# USB_Downstream_Type_C_Port_4.net
KiCad netlist of a schematic drawn in Altium Designer
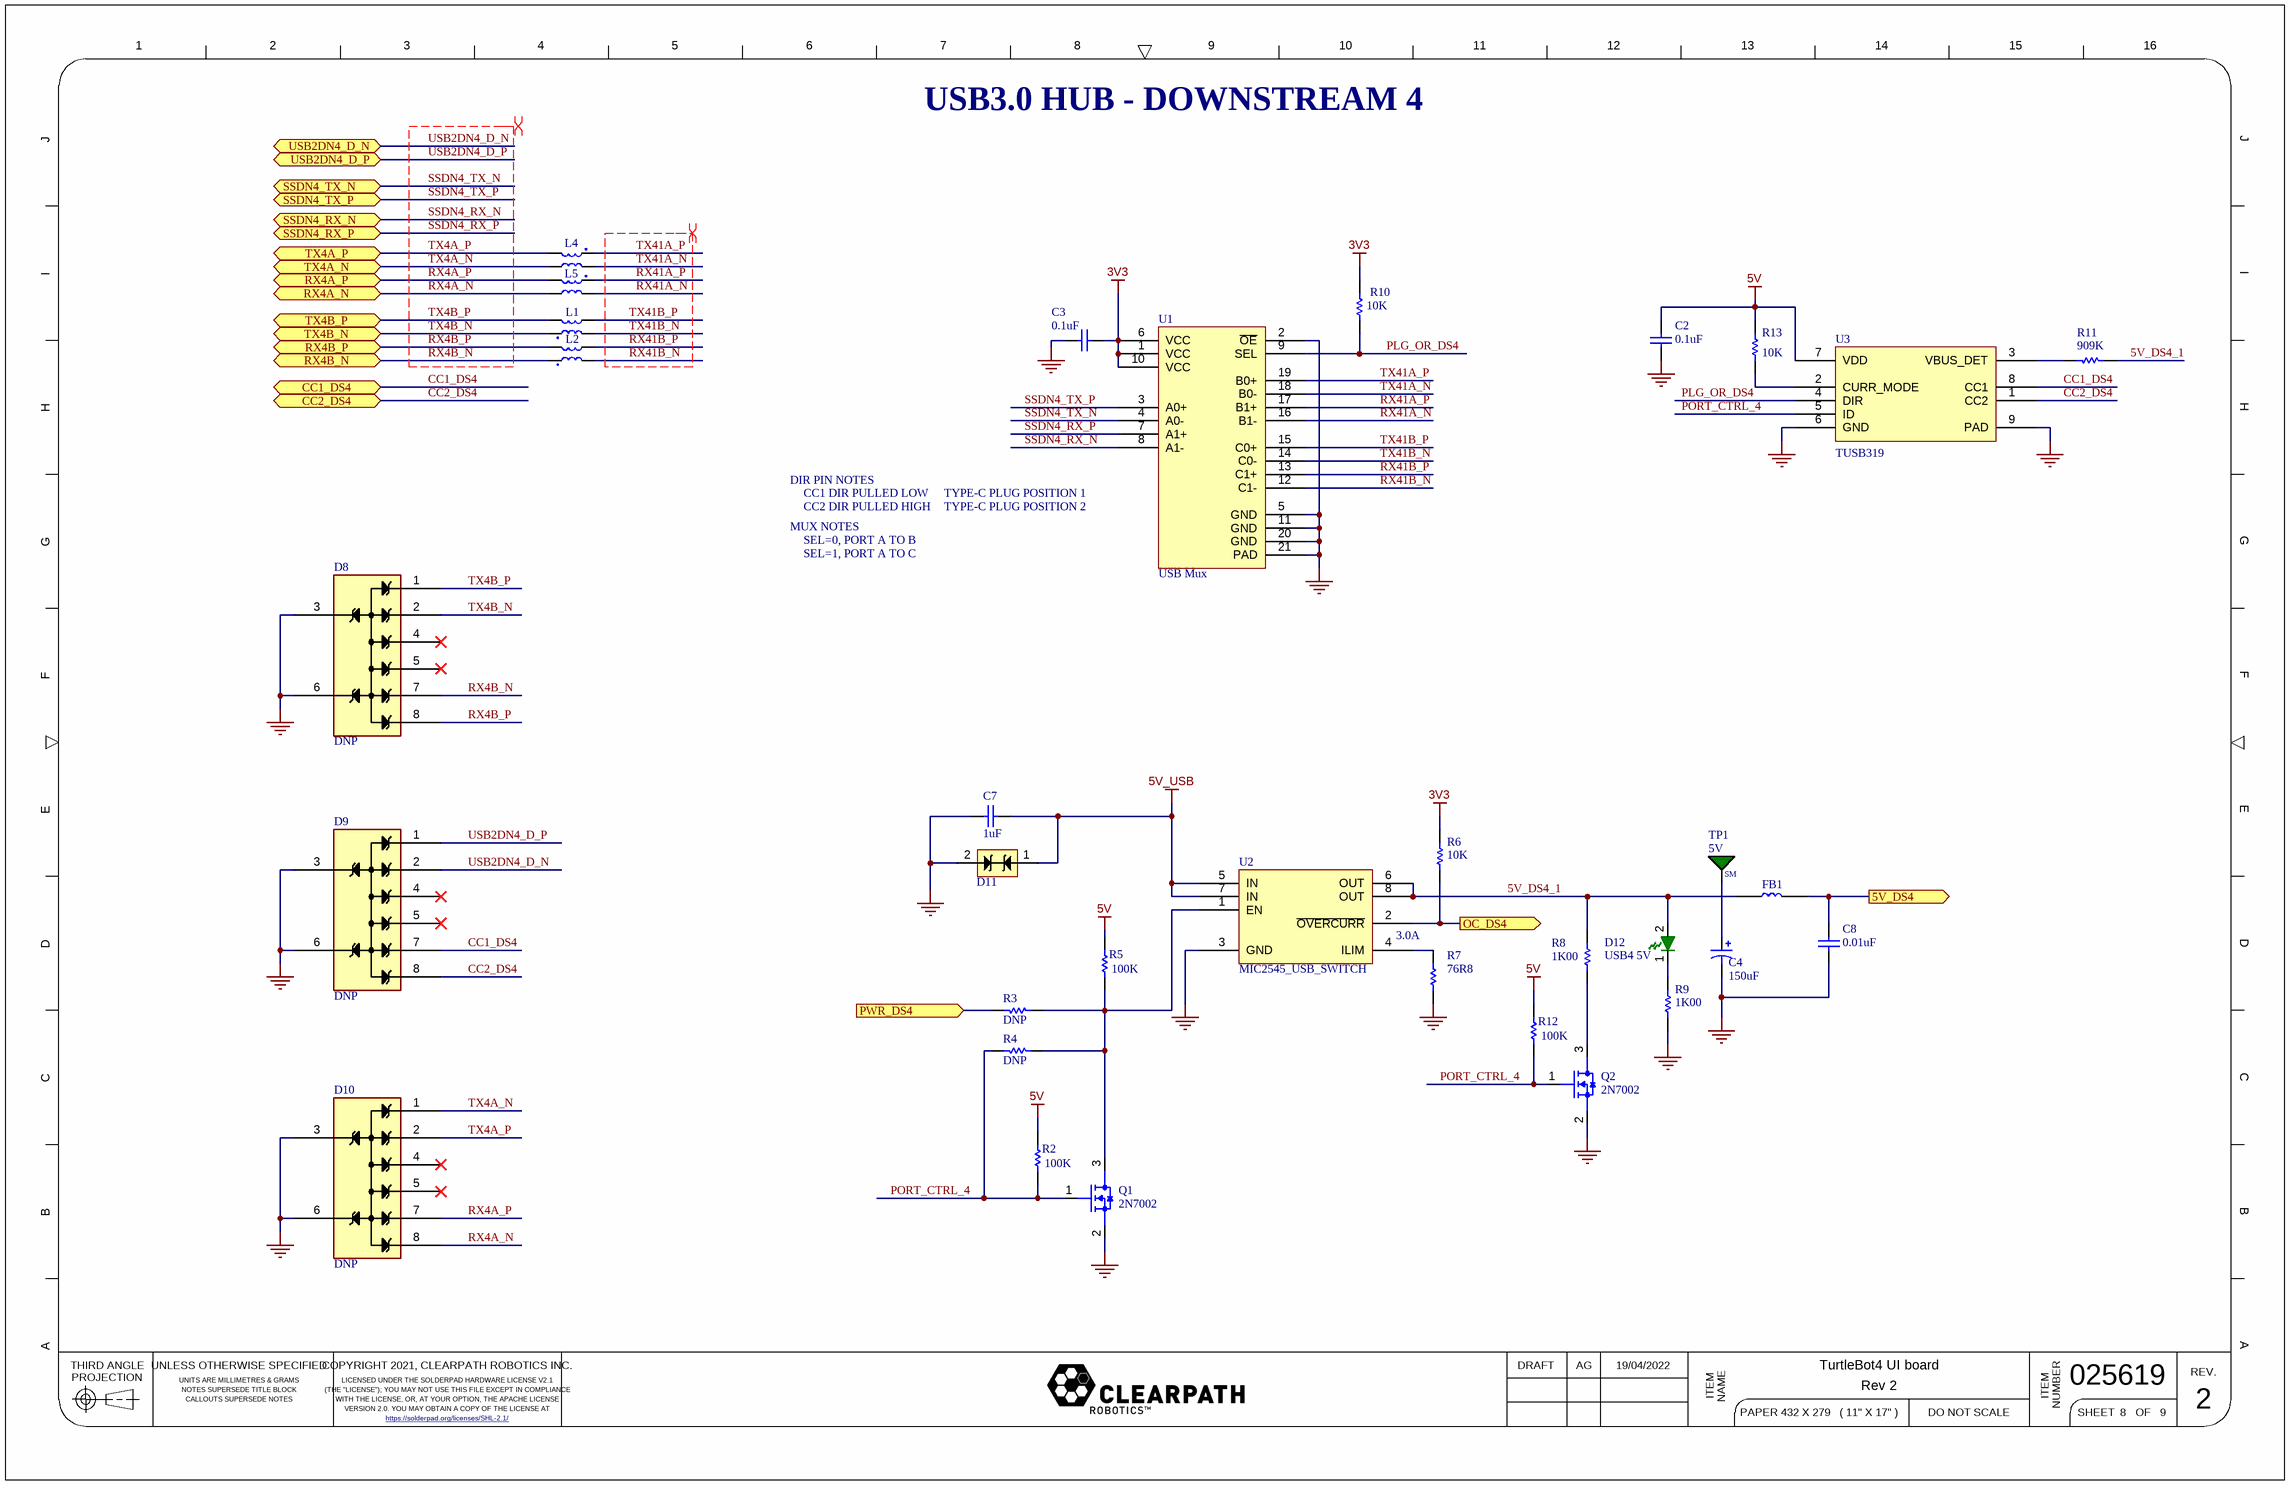
[diagram p0: USB Downstream Type C Port 4.SchDoc]

(export (version "E")
  (design (tool "Eeschema 10.0.6"))
  (components
    (comp (ref "C2")
      (value "0.1uF")
      (footprint "C0805")
      (description "Capacitor")
      (fields (field (name "TOLERANCE") "10%") (field (name "VOLTAGE") "50V"))
      (libsource (lib "CPR_CommonDevices") (part "Capacitor _SMT"))
    )
    (comp (ref "C3")
      (value "0.1uF")
      (footprint "C0805")
      (description "Capacitor")
      (fields (field (name "TOLERANCE") "10%") (field (name "VOLTAGE") "50V"))
      (libsource (lib "CPR_CommonDevices") (part "Capacitor _SMT"))
    )
    (comp (ref "C4")
      (value "150uF")
      (footprint "T494D157K016AT:CAPMP7.6X4.3_3.1N_KEM-M")
      (description "CAP TANT 150UF 10% 16V 2917")
      (fields (field (name "VOLTAGE") "16V") (field (name "TOLERANCE") "10%"))
      (libsource (lib "Miscellaneous Devices") (part "Cap Pol1"))
    )
    (comp (ref "C7")
      (value "1uF")
      (footprint "C0805")
      (description "Capacitor")
      (fields (field (name "TOLERANCE") "-20 +80") (field (name "VOLTAGE") "50V"))
      (libsource (lib "CPR_CommonDevices") (part "Capacitor _SMT"))
    )
    (comp (ref "C8")
      (value "0.01uF")
      (footprint "C0805")
      (description "Capacitor")
      (fields (field (name "TOLERANCE") "10%") (field (name "VOLTAGE") "50V"))
      (libsource (lib "CPR_CommonDevices") (part "Capacitor _SMT"))
    )
    (comp (ref "D8")
      (value "DNP")
      (footprint "ESD7016")
      (description "USB3 TVS diode assy")
      (fields (field (name "MFG") "ON Semi"))
      (libsource (lib "ONSemi_ESD7016") (part "ESD7016"))
    )
    (comp (ref "D9")
      (value "DNP")
      (footprint "ESD7016")
      (description "USB3 TVS diode assy")
      (fields (field (name "MFG") "ON Semi"))
      (libsource (lib "ONSemi_ESD7016") (part "ESD7016"))
    )
    (comp (ref "D10")
      (value "DNP")
      (footprint "ESD7016")
      (description "USB3 TVS diode assy")
      (fields (field (name "MFG") "ON Semi"))
      (libsource (lib "ONSemi_ESD7016") (part "ESD7016"))
    )
    (comp (ref "D11")
      (value "TVS DIODE BIDIR 15V SMC")
      (footprint "General PCB Library:DO-214AA")
      (description "TVS 600W 15V BI-DIR DO-214AA")
      (fields (field (name "MFG") "Littelfuse Inc."))
      (libsource (lib "SMBJ15CA") (part "TVS DIODE BIDIR 15V SMC"))
    )
    (comp (ref "D12")
      (value "USB4 5V")
      (footprint "LED_0805_GRN")
      (description "Green LED")
      (fields (field (name "MFG") "LiteOn"))
      (libsource (lib "Green LED") (part "GREEN_LED"))
    )
    (comp (ref "FB1")
      (value "742792602")
      (footprint "General PCB Library:R0603")
      (description "60 Ohms 1 Signal Line Ferrite Bead 0603 (1608 Metric) 3A 40mOhm")
      (libsource (lib "742792602") (part "742792602"))
    )
    (comp (ref "L1")
      (value "CMC 100MA 2LN 90 OHM SMD2")
      (footprint "cmc_90_ohms:cmc_90_ohms")
      (description "Line Common Mode Choke Surface Mount 90 Ohms 100mA DCR 5Ohm")
      (libsource (lib "cmc_90_ohms") (part "CMC 90_Ohms"))
    )
    (comp (ref "L2")
      (value "CMC 100MA 2LN 90 OHM SMD2")
      (footprint "cmc_90_ohms:cmc_90_ohms")
      (description "Line Common Mode Choke Surface Mount 90 Ohms 100mA DCR 5Ohm")
      (libsource (lib "cmc_90_ohms") (part "CMC 90_Ohms"))
    )
    (comp (ref "L4")
      (value "CMC 100MA 2LN 90 OHM SMD2")
      (footprint "cmc_90_ohms:cmc_90_ohms")
      (description "Line Common Mode Choke Surface Mount 90 Ohms 100mA DCR 5Ohm")
      (libsource (lib "cmc_90_ohms") (part "CMC 90_Ohms"))
    )
    (comp (ref "L5")
      (value "CMC 100MA 2LN 90 OHM SMD2")
      (footprint "cmc_90_ohms:cmc_90_ohms")
      (description "Line Common Mode Choke Surface Mount 90 Ohms 100mA DCR 5Ohm")
      (libsource (lib "cmc_90_ohms") (part "CMC 90_Ohms"))
    )
    (comp (ref "Q1")
      (value "NFET")
      (footprint "SOT-23-3")
      (fields (field (name "MFG PN") "2N7002") (field (name "MFG") "ON Semi"))
      (libsource (lib "NFET_SINGLE") (part "NFET_SNGL"))
    )
    (comp (ref "Q2")
      (value "NFET")
      (footprint "SOT-23-3")
      (fields (field (name "MFG PN") "2N7002") (field (name "MFG") "ON Semi"))
      (libsource (lib "NFET_SINGLE") (part "NFET_SNGL"))
    )
    (comp (ref "R2")
      (value "100K")
      (footprint "R0805")
      (description "Resistor")
      (fields (field (name "TOLERANCE") "1%") (field (name "MFG") "Yageo"))
      (libsource (lib "") (part "Resistor_SMT_1"))
    )
    (comp (ref "R3")
      (value "DNP")
      (footprint "R0805")
      (description "Resistor")
      (fields (field (name "MFG") "Yageo") (field (name "Comment") "Resistor_SMT"))
      (libsource (lib "CPR_CommonDevices") (part "Resistor_SMT"))
    )
    (comp (ref "R4")
      (value "DNP")
      (footprint "R0805")
      (description "Resistor")
      (fields (field (name "MFG") "Yageo") (field (name "Comment") "Resistor_SMT"))
      (libsource (lib "CPR_CommonDevices") (part "Resistor_SMT"))
    )
    (comp (ref "R5")
      (value "100K")
      (footprint "R0805")
      (description "Resistor")
      (fields (field (name "TOLERANCE") "1%") (field (name "MFG") "Yageo"))
      (libsource (lib "") (part "Resistor_SMT_1"))
    )
    (comp (ref "R6")
      (value "10K")
      (footprint "R0805")
      (description "Resistor")
      (fields (field (name "TOLERANCE") "1%") (field (name "MFG") "Yageo"))
      (libsource (lib "") (part "Resistor_SMT_1"))
    )
    (comp (ref "R7")
      (value "3.0A")
      (footprint "R0805")
      (description "Resistor")
      (fields
        (field (name "ALTIUM_VALUE") "76R8")
        (field (name "TOLERANCE") "1%")
        (field (name "MFG") "Yageo")
      )
      (libsource (lib "") (part "Resistor_SMT_1"))
    )
    (comp (ref "R8")
      (value "1K00")
      (footprint "R0805")
      (description "Resistor")
      (fields (field (name "TOLERANCE") "1%") (field (name "MFG") "Yageo"))
      (libsource (lib "") (part "Resistor_SMT_1"))
    )
    (comp (ref "R9")
      (value "1K00")
      (footprint "R0805")
      (description "Resistor")
      (fields (field (name "TOLERANCE") "1%") (field (name "MFG") "Yageo"))
      (libsource (lib "") (part "Resistor_SMT_1"))
    )
    (comp (ref "R10")
      (value "10K")
      (footprint "R0805")
      (description "Resistor")
      (fields (field (name "TOLERANCE") "1%") (field (name "MFG") "Yageo"))
      (libsource (lib "") (part "Resistor_SMT_1"))
    )
    (comp (ref "R11")
      (value "909K")
      (footprint "R0805")
      (description "Resistor")
      (fields (field (name "TOLERANCE") "1%") (field (name "MFG") "Yageo"))
      (libsource (lib "") (part "Resistor_SMT_1"))
    )
    (comp (ref "R12")
      (value "100K")
      (footprint "R0805")
      (description "Resistor")
      (fields (field (name "TOLERANCE") "1%") (field (name "MFG") "Yageo"))
      (libsource (lib "") (part "Resistor_SMT_1"))
    )
    (comp (ref "R13")
      (value "10K")
      (footprint "R0805")
      (description "Resistor")
      (fields (field (name "TOLERANCE") "1%") (field (name "MFG") "Yageo"))
      (libsource (lib "") (part "Resistor_SMT_1"))
    )
    (comp (ref "TP1")
      (value "5V")
      (footprint "TP_28SM")
      (description "Test point, 28 Mil exposed pad")
      (fields (field (name "MANUFACTURER") "Clearpath Robotics Inc."))
      (libsource (lib "Test Points") (part "TP_28SM"))
    )
    (comp (ref "U1")
      (value "USB Mux")
      (footprint "TQFN20")
      (description "TC7PCI3212MT,LF USB3.0 Mux")
      (fields (field (name "MANUFACTURER") "Toshiba"))
      (libsource (lib "TOSHIBA TC7PCI3212MT") (part "TC7PCI3212"))
    )
    (comp (ref "U2")
      (value "MIC2545_USB_SWITCH")
      (footprint "SOIC-8-150")
      (description "IC PWR SWITCH N-CHAN 1:1 8SOIC")
      (fields (field (name "MFG") "Microchip"))
      (libsource (lib "MIC2545") (part "MIC2545_USB_SWITCH"))
    )
    (comp (ref "U3")
      (value "TUSB319")
      (footprint "WSON8")
      (description "USB Type C Controller")
      (fields (field (name "MFG") "Texas Instruments"))
      (libsource (lib "TUSB319") (part "TUSB319"))
    )
  )
  (nets
    (net (code "1") (name "/5V_DS4") (class "Default")
      (node (ref "C8") (pin "1") (pinfunction "1_1") (pintype "passive"))
      (node (ref "FB1") (pin "2") (pinfunction "2_2") (pintype "passive"))
    )
    (net (code "2") (name "/5V_DS4_1") (class "Default")
      (node (ref "D12") (pin "2") (pinfunction "RA_2") (pintype "passive"))
      (node (ref "FB1") (pin "1") (pinfunction "1_1") (pintype "passive"))
      (node (ref "R11") (pin "2") (pinfunction "2_2") (pintype "passive"))
      (node (ref "R8") (pin "1") (pinfunction "1_1") (pintype "passive"))
      (node (ref "U2") (pin "6") (pinfunction "OUT_6") (pintype "passive"))
      (node (ref "U2") (pin "8") (pinfunction "OUT_8") (pintype "passive"))
    )
    (net (code "3") (name "/CC1_DS4") (class "Default")
      (node (ref "D9") (pin "7") (pintype "passive"))
      (node (ref "U3") (pin "8") (pinfunction "CC1_8") (pintype "passive"))
    )
    (net (code "4") (name "/CC2_DS4") (class "Default")
      (node (ref "D9") (pin "8") (pintype "passive"))
      (node (ref "U3") (pin "1") (pinfunction "CC2_1") (pintype "passive"))
    )
    (net (code "5") (name "/OC_DS4") (class "Default")
      (node (ref "R6") (pin "2") (pinfunction "2_2") (pintype "passive"))
      (node (ref "U2") (pin "2") (pinfunction "~{OVERCURR}_2") (pintype "passive"))
    )
    (net (code "6") (name "/PLG_OR_DS4") (class "Default")
      (node (ref "R10") (pin "2") (pinfunction "2_2") (pintype "passive"))
      (node (ref "U1") (pin "9") (pinfunction "SEL_9") (pintype "passive"))
      (node (ref "U3") (pin "4") (pinfunction "DIR_4") (pintype "passive"))
    )
    (net (code "7") (name "/PORT_CTRL_4") (class "Default")
      (node (ref "Q1") (pin "1") (pinfunction "G1_1") (pintype "passive"))
      (node (ref "Q2") (pin "1") (pinfunction "G1_1") (pintype "passive"))
      (node (ref "R12") (pin "1") (pinfunction "1_1") (pintype "passive"))
      (node (ref "R2") (pin "1") (pinfunction "1_1") (pintype "passive"))
      (node (ref "R4") (pin "1") (pinfunction "1_1") (pintype "passive"))
      (node (ref "U3") (pin "5") (pinfunction "ID_5") (pintype "passive"))
    )
    (net (code "8") (name "/PWR_DS4") (class "Default")
      (node (ref "R3") (pin "1") (pinfunction "1_1") (pintype "passive"))
    )
    (net (code "9") (name "/RX4A_N") (class "Default")
      (node (ref "D10") (pin "8") (pintype "passive"))
      (node (ref "L5") (pin "3") (pinfunction "3_3") (pintype "passive"))
    )
    (net (code "10") (name "/RX4A_P") (class "Default")
      (node (ref "D10") (pin "7") (pintype "passive"))
      (node (ref "L5") (pin "4") (pinfunction "4_4") (pintype "passive"))
    )
    (net (code "11") (name "/RX4B_N") (class "Default")
      (node (ref "D8") (pin "7") (pintype "passive"))
      (node (ref "L2") (pin "1") (pinfunction "1_1") (pintype "passive"))
    )
    (net (code "12") (name "/RX4B_P") (class "Default")
      (node (ref "D8") (pin "8") (pintype "passive"))
      (node (ref "L2") (pin "2") (pinfunction "2_2") (pintype "passive"))
    )
    (net (code "13") (name "/RX41A_N") (class "Default")
      (node (ref "L5") (pin "2") (pinfunction "2_2") (pintype "passive"))
      (node (ref "U1") (pin "16") (pinfunction "B1-_16") (pintype "passive"))
    )
    (net (code "14") (name "/RX41A_P") (class "Default")
      (node (ref "L5") (pin "1") (pinfunction "1_1") (pintype "passive"))
      (node (ref "U1") (pin "17") (pinfunction "B1+_17") (pintype "passive"))
    )
    (net (code "15") (name "/RX41B_N") (class "Default")
      (node (ref "L2") (pin "4") (pinfunction "4_4") (pintype "passive"))
      (node (ref "U1") (pin "12") (pinfunction "C1-_12") (pintype "passive"))
    )
    (net (code "16") (name "/RX41B_P") (class "Default")
      (node (ref "L2") (pin "3") (pinfunction "3_3") (pintype "passive"))
      (node (ref "U1") (pin "13") (pinfunction "C1+_13") (pintype "passive"))
    )
    (net (code "17") (name "/SSDN4_RX_N") (class "Default")
      (node (ref "U1") (pin "8") (pinfunction "A1-_8") (pintype "passive"))
    )
    (net (code "18") (name "/SSDN4_RX_P") (class "Default")
      (node (ref "U1") (pin "7") (pinfunction "A1+_7") (pintype "passive"))
    )
    (net (code "19") (name "/SSDN4_TX_N") (class "Default")
      (node (ref "U1") (pin "4") (pinfunction "A0-_4") (pintype "passive"))
    )
    (net (code "20") (name "/SSDN4_TX_P") (class "Default")
      (node (ref "U1") (pin "3") (pinfunction "A0+_3") (pintype "passive"))
    )
    (net (code "21") (name "/TX4A_N") (class "Default")
      (node (ref "D10") (pin "1") (pinfunction "1_1") (pintype "passive"))
      (node (ref "L4") (pin "3") (pinfunction "3_3") (pintype "passive"))
    )
    (net (code "22") (name "/TX4A_P") (class "Default")
      (node (ref "D10") (pin "2") (pintype "passive"))
      (node (ref "L4") (pin "4") (pinfunction "4_4") (pintype "passive"))
    )
    (net (code "23") (name "/TX4B_N") (class "Default")
      (node (ref "D8") (pin "2") (pintype "passive"))
      (node (ref "L1") (pin "1") (pinfunction "1_1") (pintype "passive"))
    )
    (net (code "24") (name "/TX4B_P") (class "Default")
      (node (ref "D8") (pin "1") (pinfunction "1_1") (pintype "passive"))
      (node (ref "L1") (pin "2") (pinfunction "2_2") (pintype "passive"))
    )
    (net (code "25") (name "/TX41A_N") (class "Default")
      (node (ref "L4") (pin "2") (pinfunction "2_2") (pintype "passive"))
      (node (ref "U1") (pin "18") (pinfunction "B0-_18") (pintype "passive"))
    )
    (net (code "26") (name "/TX41A_P") (class "Default")
      (node (ref "L4") (pin "1") (pinfunction "1_1") (pintype "passive"))
      (node (ref "U1") (pin "19") (pinfunction "B0+_19") (pintype "passive"))
    )
    (net (code "27") (name "/TX41B_N") (class "Default")
      (node (ref "L1") (pin "4") (pinfunction "4_4") (pintype "passive"))
      (node (ref "U1") (pin "14") (pinfunction "C0-_14") (pintype "passive"))
    )
    (net (code "28") (name "/TX41B_P") (class "Default")
      (node (ref "L1") (pin "3") (pinfunction "3_3") (pintype "passive"))
      (node (ref "U1") (pin "15") (pinfunction "C0+_15") (pintype "passive"))
    )
    (net (code "29") (name "/USB2DN4_D_N") (class "Default") (node (ref "D9") (pin "2") (pintype "passive")))
    (net (code "30") (name "/USB2DN4_D_P") (class "Default")
      (node (ref "D9") (pin "1") (pinfunction "1_1") (pintype "passive"))
    )
    (net (code "31") (name "3V3") (class "Default")
      (node (ref "C3") (pin "1") (pinfunction "1_1") (pintype "passive"))
      (node (ref "R10") (pin "1") (pinfunction "1_1") (pintype "passive"))
      (node (ref "R6") (pin "1") (pinfunction "1_1") (pintype "passive"))
      (node (ref "U1") (pin "1") (pinfunction "VCC_1") (pintype "passive"))
      (node (ref "U1") (pin "10") (pinfunction "VCC_10") (pintype "passive"))
      (node (ref "U1") (pin "6") (pinfunction "VCC_6") (pintype "passive"))
    )
    (net (code "32") (name "5V") (class "Default")
      (node (ref "C2") (pin "1") (pinfunction "1_1") (pintype "passive"))
      (node (ref "R12") (pin "2") (pinfunction "2_2") (pintype "passive"))
      (node (ref "R13") (pin "1") (pinfunction "1_1") (pintype "passive"))
      (node (ref "R2") (pin "2") (pinfunction "2_2") (pintype "passive"))
      (node (ref "R5") (pin "2") (pinfunction "2_2") (pintype "passive"))
      (node (ref "U3") (pin "7") (pinfunction "VDD_7") (pintype "passive"))
    )
    (net (code "33") (name "5V_USB") (class "Default")
      (node (ref "C7") (pin "2") (pinfunction "2_2") (pintype "passive"))
      (node (ref "D11") (pin "1") (pintype "passive"))
      (node (ref "U2") (pin "5") (pinfunction "IN_5") (pintype "passive"))
      (node (ref "U2") (pin "7") (pinfunction "IN_7") (pintype "passive"))
    )
    (net (code "34") (name "GND") (class "Default")
      (node (ref "C2") (pin "2") (pinfunction "2_2") (pintype "passive"))
      (node (ref "C3") (pin "2") (pinfunction "2_2") (pintype "passive"))
      (node (ref "C4") (pin "2") (pinfunction "2_2") (pintype "passive"))
      (node (ref "C7") (pin "1") (pinfunction "1_1") (pintype "passive"))
      (node (ref "C8") (pin "2") (pinfunction "2_2") (pintype "passive"))
      (node (ref "D10") (pin "3") (pintype "passive"))
      (node (ref "D10") (pin "6") (pintype "passive"))
      (node (ref "D11") (pin "2") (pintype "passive"))
      (node (ref "D8") (pin "3") (pintype "passive"))
      (node (ref "D8") (pin "6") (pintype "passive"))
      (node (ref "D9") (pin "3") (pintype "passive"))
      (node (ref "D9") (pin "6") (pintype "passive"))
      (node (ref "Q1") (pin "2") (pinfunction "D1_2") (pintype "passive"))
      (node (ref "Q2") (pin "2") (pinfunction "D1_2") (pintype "passive"))
      (node (ref "R7") (pin "1") (pinfunction "1_1") (pintype "passive"))
      (node (ref "R9") (pin "2") (pinfunction "2_2") (pintype "passive"))
      (node (ref "U1") (pin "11") (pinfunction "GND_11") (pintype "passive"))
      (node (ref "U1") (pin "2") (pinfunction "~{OE}_2") (pintype "passive"))
      (node (ref "U1") (pin "20") (pinfunction "GND_20") (pintype "passive"))
      (node (ref "U1") (pin "21") (pinfunction "PAD_21") (pintype "passive"))
      (node (ref "U1") (pin "5") (pinfunction "GND_5") (pintype "passive"))
      (node (ref "U2") (pin "3") (pinfunction "GND_3") (pintype "passive"))
      (node (ref "U3") (pin "6") (pinfunction "GND_6") (pintype "passive"))
      (node (ref "U3") (pin "9") (pinfunction "PAD_9") (pintype "passive"))
    )
    (net (code "35") (name "Net-(C4-Pad1)") (class "Default")
      (node (ref "C4") (pin "1") (pinfunction "1_1") (pintype "passive"))
      (node (ref "TP1") (pin "1") (pintype "passive"))
    )
    (net (code "36") (name "Net-(D12-RK)") (class "Default")
      (node (ref "D12") (pin "1") (pinfunction "RK_1") (pintype "passive"))
      (node (ref "R9") (pin "1") (pinfunction "1_1") (pintype "passive"))
    )
    (net (code "37") (name "Net-(Q1-S1)") (class "Default")
      (node (ref "Q1") (pin "3") (pinfunction "S1_3") (pintype "passive"))
      (node (ref "R3") (pin "2") (pinfunction "2_2") (pintype "passive"))
      (node (ref "R4") (pin "2") (pinfunction "2_2") (pintype "passive"))
      (node (ref "R5") (pin "1") (pinfunction "1_1") (pintype "passive"))
      (node (ref "U2") (pin "1") (pinfunction "EN_1") (pintype "passive"))
    )
    (net (code "38") (name "Net-(Q2-S1)") (class "Default")
      (node (ref "Q2") (pin "3") (pinfunction "S1_3") (pintype "passive"))
      (node (ref "R8") (pin "2") (pinfunction "2_2") (pintype "passive"))
    )
    (net (code "39") (name "Net-(U2-ILIM)") (class "Default")
      (node (ref "R7") (pin "2") (pinfunction "2_2") (pintype "passive"))
      (node (ref "U2") (pin "4") (pinfunction "ILIM_4") (pintype "passive"))
    )
    (net (code "40") (name "Net-(U3-CURR_MODE)") (class "Default")
      (node (ref "R13") (pin "2") (pinfunction "2_2") (pintype "passive"))
      (node (ref "U3") (pin "2") (pinfunction "CURR_MODE_2") (pintype "passive"))
    )
    (net (code "41") (name "Net-(U3-VBUS_DET)") (class "Default")
      (node (ref "R11") (pin "1") (pinfunction "1_1") (pintype "passive"))
      (node (ref "U3") (pin "3") (pinfunction "VBUS_DET_3") (pintype "passive"))
    )
    (net (code "42") (name "unconnected-(D8-Pad4)") (class "Default")
      (node (ref "D8") (pin "4") (pintype "passive+no_connect"))
    )
    (net (code "43") (name "unconnected-(D8-Pad5)") (class "Default")
      (node (ref "D8") (pin "5") (pintype "passive+no_connect"))
    )
    (net (code "44") (name "unconnected-(D9-Pad4)") (class "Default")
      (node (ref "D9") (pin "4") (pintype "passive+no_connect"))
    )
    (net (code "45") (name "unconnected-(D9-Pad5)") (class "Default")
      (node (ref "D9") (pin "5") (pintype "passive+no_connect"))
    )
    (net (code "46") (name "unconnected-(D10-Pad4)") (class "Default")
      (node (ref "D10") (pin "4") (pintype "passive+no_connect"))
    )
    (net (code "47") (name "unconnected-(D10-Pad5)") (class "Default")
      (node (ref "D10") (pin "5") (pintype "passive+no_connect"))
    )
  )
)
